# SparkFun_Serial_USB_Adapter-iPodNike.net
KiCad netlist of a schematic drawn in EAGLE
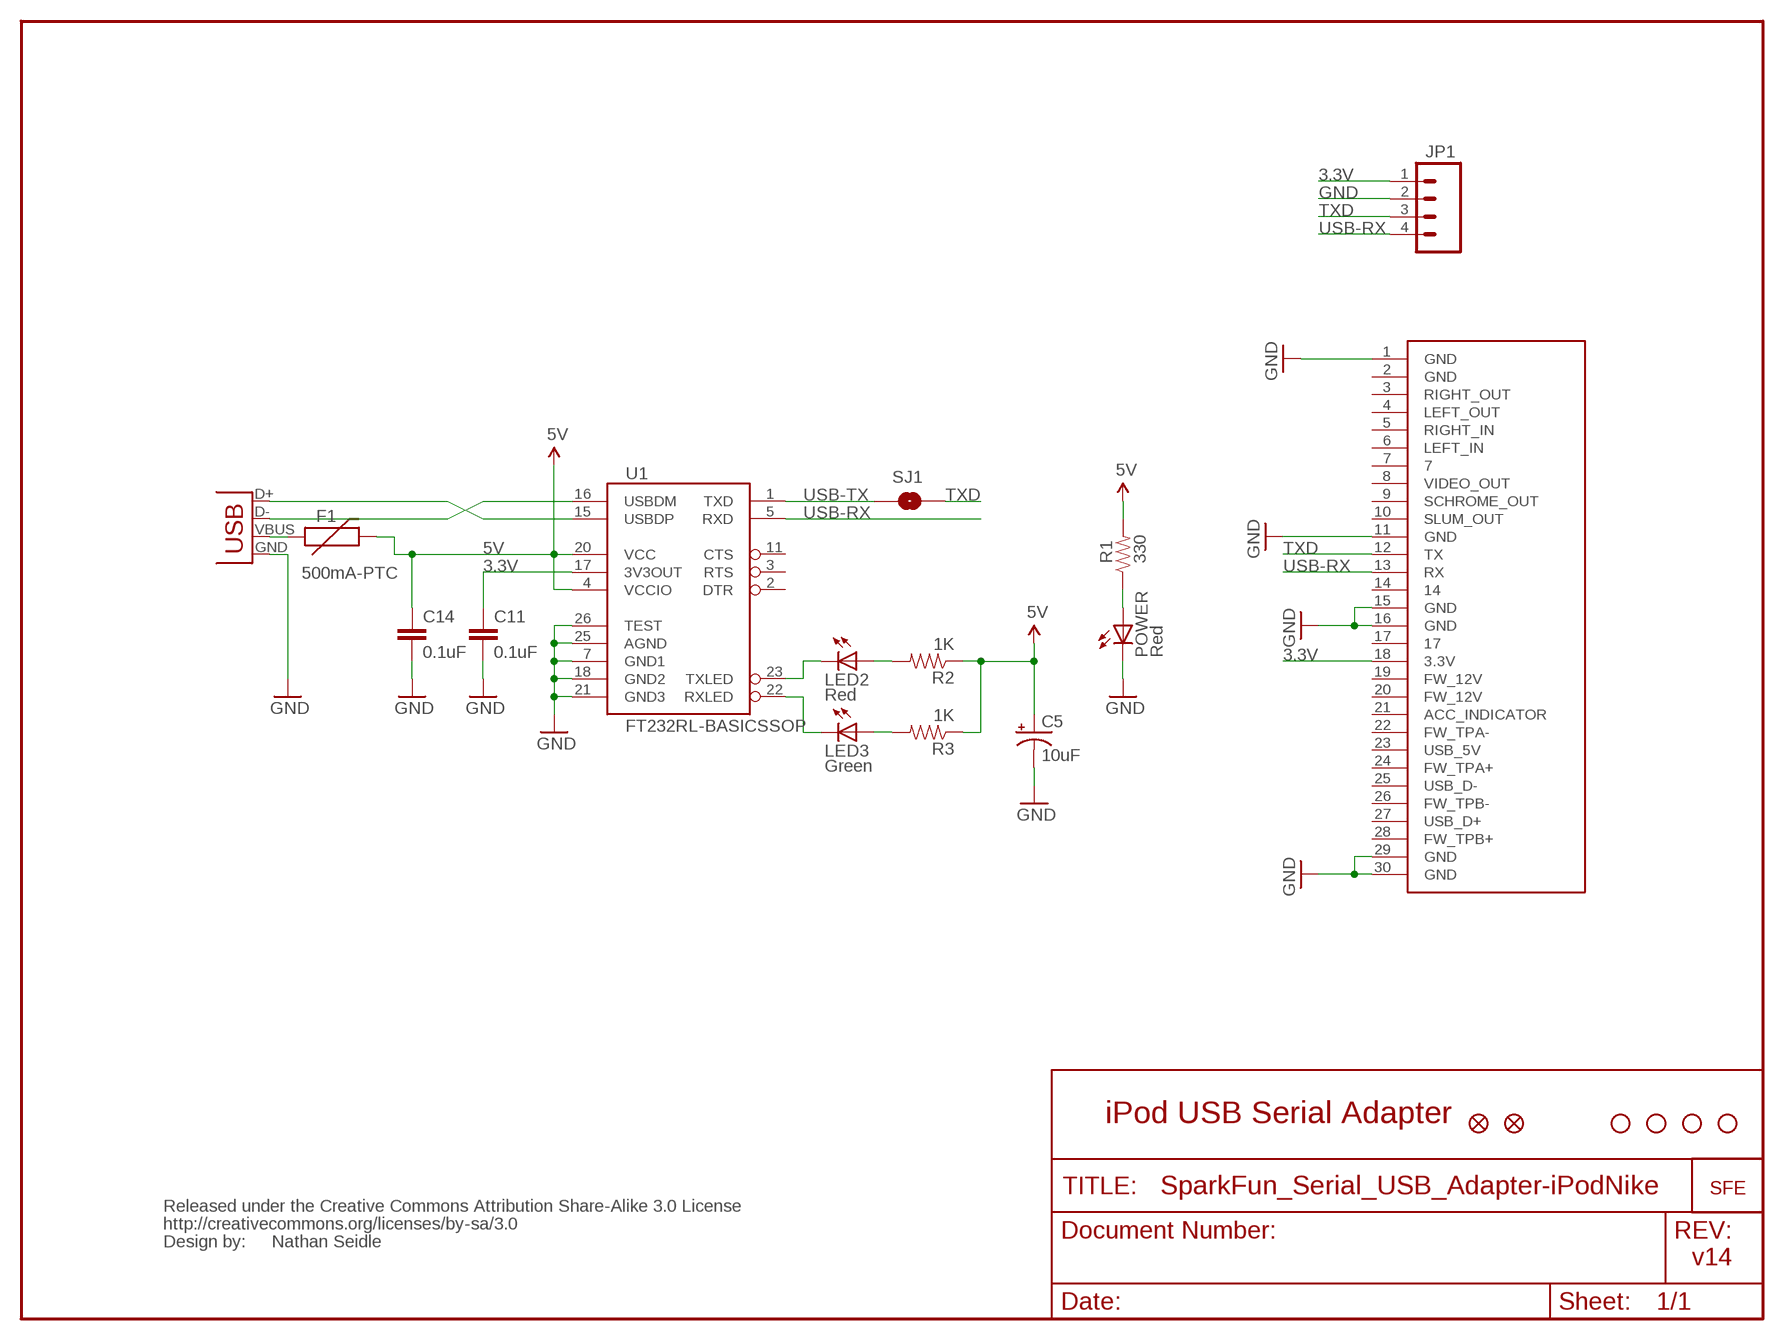
[diagram p0: schematic, sheet 1]

(export (version "E")
  (design (tool "Eeschema 10.0.6"))
  (components
    (comp (ref "C5")
      (value "10uF")
      (footprint "eagle-import:EIA3216")
      (libsource (lib "eagle-import") (part "CAP_POL1206"))
    )
    (comp (ref "C11")
      (value "0.1uF")
      (footprint "eagle-import:C0402")
      (libsource (lib "eagle-import") (part "CAP0402"))
    )
    (comp (ref "C14")
      (value "0.1uF")
      (footprint "eagle-import:C0402")
      (libsource (lib "eagle-import") (part "CAP0402"))
    )
    (comp (ref "F1")
      (value "500mA-PTC")
      (footprint "eagle-import:PTC-1206")
      (libsource (lib "eagle-import") (part "PTCSMD"))
    )
    (comp (ref "JP1")
      (value "M04PTH")
      (footprint "eagle-import:1X04")
      (libsource (lib "eagle-import") (part "M04PTH"))
    )
    (comp (ref "LED2")
      (value "Red")
      (footprint "eagle-import:LED-0603")
      (libsource (lib "eagle-import") (part "LED0603"))
    )
    (comp (ref "LED3")
      (value "Green")
      (footprint "eagle-import:LED-0603")
      (libsource (lib "eagle-import") (part "LED0603"))
    )
    (comp (ref "POWER")
      (value "Red")
      (footprint "eagle-import:LED-0603")
      (libsource (lib "eagle-import") (part "LED0603"))
    )
    (comp (ref "R1")
      (value "330")
      (footprint "eagle-import:C0402")
      (libsource (lib "eagle-import") (part "RESISTOR0402"))
    )
    (comp (ref "R2")
      (value "1K")
      (footprint "eagle-import:C0402")
      (libsource (lib "eagle-import") (part "RESISTOR0402"))
    )
    (comp (ref "R3")
      (value "1K")
      (footprint "eagle-import:C0402")
      (libsource (lib "eagle-import") (part "RESISTOR0402"))
    )
    (comp (ref "SJ1")
      (value "SOLDERJUMPERNC2")
      (footprint "eagle-import:SJ_2S")
      (libsource (lib "eagle-import") (part "SOLDERJUMPERNC2"))
    )
    (comp (ref "U$1")
      (value "STAND-OFF")
      (footprint "eagle-import:STAND-OFF")
      (libsource (lib "eagle-import") (part "STAND-OFF"))
    )
    (comp (ref "U$2")
      (value "IPOD_CONNECTOR_FEMALE")
      (footprint "eagle-import:IPOD_FEMALE_CONNECTOR")
      (libsource (lib "eagle-import") (part "IPOD_CONNECTOR_FEMALE"))
    )
    (comp (ref "U$3")
      (value "LOGO-SFENEW")
      (footprint "eagle-import:SFE-NEW-WEBLOGO")
      (libsource (lib "eagle-import") (part "LOGO-SFENEW"))
    )
    (comp (ref "U$4")
      (value "FIDUCIAL1X2")
      (footprint "eagle-import:FIDUCIAL-1X2")
      (libsource (lib "eagle-import") (part "FIDUCIAL1X2"))
    )
    (comp (ref "U$5")
      (value "STAND-OFF")
      (footprint "eagle-import:STAND-OFF")
      (libsource (lib "eagle-import") (part "STAND-OFF"))
    )
    (comp (ref "U$6")
      (value "STAND-OFF")
      (footprint "eagle-import:STAND-OFF")
      (libsource (lib "eagle-import") (part "STAND-OFF"))
    )
    (comp (ref "U$7")
      (value "STAND-OFF")
      (footprint "eagle-import:STAND-OFF")
      (libsource (lib "eagle-import") (part "STAND-OFF"))
    )
    (comp (ref "U$8")
      (value "FIDUCIAL1X2")
      (footprint "eagle-import:FIDUCIAL-1X2")
      (libsource (lib "eagle-import") (part "FIDUCIAL1X2"))
    )
    (comp (ref "U$9")
      (value "CREATIVE_COMMONS")
      (footprint "eagle-import:CREATIVE_COMMONS")
      (libsource (lib "eagle-import") (part "CREATIVE_COMMONS"))
    )
    (comp (ref "U1")
      (value "FT232RL-BASICSSOP")
      (footprint "eagle-import:SSOP28DB")
      (libsource (lib "eagle-import") (part "FT232RL-BASICSSOP"))
    )
    (comp (ref "X1")
      (value "USBSMD")
      (footprint "eagle-import:USB-MINIB")
      (libsource (lib "eagle-import") (part "USBSMD"))
    )
  )
  (nets
    (net (code "1") (name "/3.3V") (class "Default")
      (node (ref "C11") (pin "1") (pinfunction "1_1") (pintype "passive"))
      (node (ref "JP1") (pin "1") (pinfunction "1_1") (pintype "passive"))
      (node (ref "U$2") (pin "18") (pinfunction "3.3V_18") (pintype "bidirectional"))
      (node (ref "U1") (pin "17") (pinfunction "3V3OUT_17") (pintype "output"))
    )
    (net (code "2") (name "/TXD") (class "Default")
      (node (ref "JP1") (pin "3") (pinfunction "3_3") (pintype "passive"))
      (node (ref "SJ1") (pin "2") (pinfunction "2_2") (pintype "passive"))
      (node (ref "U$2") (pin "12") (pinfunction "TX_12") (pintype "bidirectional"))
    )
    (net (code "3") (name "/USB-RX") (class "Default")
      (node (ref "JP1") (pin "4") (pinfunction "4_4") (pintype "passive"))
      (node (ref "U$2") (pin "13") (pinfunction "RX_13") (pintype "bidirectional"))
      (node (ref "U1") (pin "5") (pinfunction "RXD_5") (pintype "input"))
    )
    (net (code "4") (name "/USB-TX") (class "Default")
      (node (ref "SJ1") (pin "1") (pinfunction "1_1") (pintype "passive"))
      (node (ref "U1") (pin "1") (pinfunction "TXD_1") (pintype "output"))
    )
    (net (code "5") (name "5V") (class "Default")
      (node (ref "C14") (pin "1") (pinfunction "1_1") (pintype "passive"))
      (node (ref "C5") (pin "A") (pinfunction "+_A") (pintype "passive"))
      (node (ref "F1") (pin "2") (pinfunction "2_2") (pintype "bidirectional"))
      (node (ref "R1") (pin "2") (pinfunction "2_2") (pintype "passive"))
      (node (ref "R2") (pin "1") (pinfunction "1_1") (pintype "passive"))
      (node (ref "R3") (pin "1") (pinfunction "1_1") (pintype "passive"))
      (node (ref "U1") (pin "20") (pinfunction "VCC_20") (pintype "power_in"))
      (node (ref "U1") (pin "4") (pinfunction "VCCIO_4") (pintype "power_in"))
    )
    (net (code "6") (name "GND") (class "Default")
      (node (ref "C11") (pin "2") (pinfunction "2_2") (pintype "passive"))
      (node (ref "C14") (pin "2") (pinfunction "2_2") (pintype "passive"))
      (node (ref "C5") (pin "C") (pinfunction "-_C") (pintype "passive"))
      (node (ref "JP1") (pin "2") (pinfunction "2_2") (pintype "passive"))
      (node (ref "POWER") (pin "C") (pinfunction "C_C") (pintype "passive"))
      (node (ref "U$2") (pin "1") (pinfunction "GND_1") (pintype "bidirectional"))
      (node (ref "U$2") (pin "11") (pinfunction "GND_11") (pintype "bidirectional"))
      (node (ref "U$2") (pin "15") (pinfunction "GND_15") (pintype "bidirectional"))
      (node (ref "U$2") (pin "16") (pinfunction "GND_16") (pintype "bidirectional"))
      (node (ref "U$2") (pin "29") (pinfunction "GND_29") (pintype "bidirectional"))
      (node (ref "U$2") (pin "30") (pinfunction "GND_30") (pintype "bidirectional"))
      (node (ref "U1") (pin "18") (pinfunction "GND2_18") (pintype "power_in"))
      (node (ref "U1") (pin "21") (pinfunction "GND3_21") (pintype "power_in"))
      (node (ref "U1") (pin "25") (pinfunction "AGND_25") (pintype "power_in"))
      (node (ref "U1") (pin "26") (pinfunction "TEST_26") (pintype "input"))
      (node (ref "U1") (pin "7") (pinfunction "GND1_7") (pintype "power_in"))
      (node (ref "X1") (pin "GND") (pinfunction "GND_GND") (pintype "bidirectional"))
    )
    (net (code "7") (name "Net-(F1-Pad1)") (class "Default")
      (node (ref "F1") (pin "1") (pinfunction "1_1") (pintype "bidirectional"))
      (node (ref "X1") (pin "VBUS") (pinfunction "VBUS_VBUS") (pintype "bidirectional"))
    )
    (net (code "8") (name "Net-(LED2-PadA)") (class "Default")
      (node (ref "LED2") (pin "A") (pinfunction "A_A") (pintype "passive"))
      (node (ref "R2") (pin "2") (pinfunction "2_2") (pintype "passive"))
    )
    (net (code "9") (name "Net-(LED3-PadA)") (class "Default")
      (node (ref "LED3") (pin "A") (pinfunction "A_A") (pintype "passive"))
      (node (ref "R3") (pin "2") (pinfunction "2_2") (pintype "passive"))
    )
    (net (code "10") (name "Net-(POWER-PadA)") (class "Default")
      (node (ref "POWER") (pin "A") (pinfunction "A_A") (pintype "passive"))
      (node (ref "R1") (pin "1") (pinfunction "1_1") (pintype "passive"))
    )
    (net (code "11") (name "Net-(U1-RXLED)") (class "Default")
      (node (ref "LED3") (pin "C") (pinfunction "C_C") (pintype "passive"))
      (node (ref "U1") (pin "22") (pinfunction "RXLED_22") (pintype "bidirectional"))
    )
    (net (code "12") (name "Net-(U1-TXLED)") (class "Default")
      (node (ref "LED2") (pin "C") (pinfunction "C_C") (pintype "passive"))
      (node (ref "U1") (pin "23") (pinfunction "TXLED_23") (pintype "bidirectional"))
    )
    (net (code "13") (name "Net-(U1-USBDM)") (class "Default")
      (node (ref "U1") (pin "16") (pinfunction "USBDM_16") (pintype "bidirectional"))
      (node (ref "X1") (pin "D-") (pinfunction "D-_D-") (pintype "bidirectional"))
    )
    (net (code "14") (name "Net-(U1-USBDP)") (class "Default")
      (node (ref "U1") (pin "15") (pinfunction "USBDP_15") (pintype "bidirectional"))
      (node (ref "X1") (pin "D+") (pinfunction "D+_D+") (pintype "bidirectional"))
    )
    (net (code "15") (name "unconnected-(U$2-ACC_INDICATOR-Pad21)") (class "Default")
      (node (ref "U$2") (pin "21") (pinfunction "ACC_INDICATOR_21") (pintype "bidirectional"))
    )
    (net (code "16") (name "unconnected-(U$2-FW_12V-Pad19)") (class "Default")
      (node (ref "U$2") (pin "19") (pinfunction "FW_12V_19") (pintype "bidirectional"))
    )
    (net (code "17") (name "unconnected-(U$2-FW_12V-Pad20)") (class "Default")
      (node (ref "U$2") (pin "20") (pinfunction "FW_12V_20") (pintype "bidirectional"))
    )
    (net (code "18") (name "unconnected-(U$2-FW_TPA+-Pad24)") (class "Default")
      (node (ref "U$2") (pin "24") (pinfunction "FW_TPA+_24") (pintype "bidirectional"))
    )
    (net (code "19") (name "unconnected-(U$2-FW_TPA--Pad22)") (class "Default")
      (node (ref "U$2") (pin "22") (pinfunction "FW_TPA-_22") (pintype "bidirectional"))
    )
    (net (code "20") (name "unconnected-(U$2-FW_TPB+-Pad28)") (class "Default")
      (node (ref "U$2") (pin "28") (pinfunction "FW_TPB+_28") (pintype "bidirectional"))
    )
    (net (code "21") (name "unconnected-(U$2-FW_TPB--Pad26)") (class "Default")
      (node (ref "U$2") (pin "26") (pinfunction "FW_TPB-_26") (pintype "bidirectional"))
    )
    (net (code "22") (name "unconnected-(U$2-GND-Pad2)") (class "Default")
      (node (ref "U$2") (pin "2") (pinfunction "GND_2") (pintype "bidirectional"))
    )
    (net (code "23") (name "unconnected-(U$2-LEFT_IN-Pad6)") (class "Default")
      (node (ref "U$2") (pin "6") (pinfunction "LEFT_IN_6") (pintype "bidirectional"))
    )
    (net (code "24") (name "unconnected-(U$2-LEFT_OUT-Pad4)") (class "Default")
      (node (ref "U$2") (pin "4") (pinfunction "LEFT_OUT_4") (pintype "bidirectional"))
    )
    (net (code "25") (name "unconnected-(U$2-Pad7)") (class "Default")
      (node (ref "U$2") (pin "7") (pinfunction "7_7") (pintype "bidirectional"))
    )
    (net (code "26") (name "unconnected-(U$2-Pad14)") (class "Default")
      (node (ref "U$2") (pin "14") (pinfunction "14_14") (pintype "bidirectional"))
    )
    (net (code "27") (name "unconnected-(U$2-Pad17)") (class "Default")
      (node (ref "U$2") (pin "17") (pinfunction "17_17") (pintype "bidirectional"))
    )
    (net (code "28") (name "unconnected-(U$2-RIGHT_IN-Pad5)") (class "Default")
      (node (ref "U$2") (pin "5") (pinfunction "RIGHT_IN_5") (pintype "bidirectional"))
    )
    (net (code "29") (name "unconnected-(U$2-RIGHT_OUT-Pad3)") (class "Default")
      (node (ref "U$2") (pin "3") (pinfunction "RIGHT_OUT_3") (pintype "bidirectional"))
    )
    (net (code "30") (name "unconnected-(U$2-SCHROME_OUT-Pad9)") (class "Default")
      (node (ref "U$2") (pin "9") (pinfunction "SCHROME_OUT_9") (pintype "bidirectional"))
    )
    (net (code "31") (name "unconnected-(U$2-SLUM_OUT-Pad10)") (class "Default")
      (node (ref "U$2") (pin "10") (pinfunction "SLUM_OUT_10") (pintype "bidirectional"))
    )
    (net (code "32") (name "unconnected-(U$2-USB_5V-Pad23)") (class "Default")
      (node (ref "U$2") (pin "23") (pinfunction "USB_5V_23") (pintype "bidirectional"))
    )
    (net (code "33") (name "unconnected-(U$2-USB_D+-Pad27)") (class "Default")
      (node (ref "U$2") (pin "27") (pinfunction "USB_D+_27") (pintype "bidirectional"))
    )
    (net (code "34") (name "unconnected-(U$2-USB_D--Pad25)") (class "Default")
      (node (ref "U$2") (pin "25") (pinfunction "USB_D-_25") (pintype "bidirectional"))
    )
    (net (code "35") (name "unconnected-(U$2-VIDEO_OUT-Pad8)") (class "Default")
      (node (ref "U$2") (pin "8") (pinfunction "VIDEO_OUT_8") (pintype "bidirectional"))
    )
    (net (code "36") (name "unconnected-(U1-CTS-Pad11)") (class "Default")
      (node (ref "U1") (pin "11") (pinfunction "CTS_11") (pintype "bidirectional"))
    )
    (net (code "37") (name "unconnected-(U1-DTR-Pad2)") (class "Default")
      (node (ref "U1") (pin "2") (pinfunction "DTR_2") (pintype "bidirectional"))
    )
    (net (code "38") (name "unconnected-(U1-RTS-Pad3)") (class "Default")
      (node (ref "U1") (pin "3") (pinfunction "RTS_3") (pintype "bidirectional"))
    )
  )
)
